# Co2Det.net
KiCad netlist of a schematic drawn in EAGLE
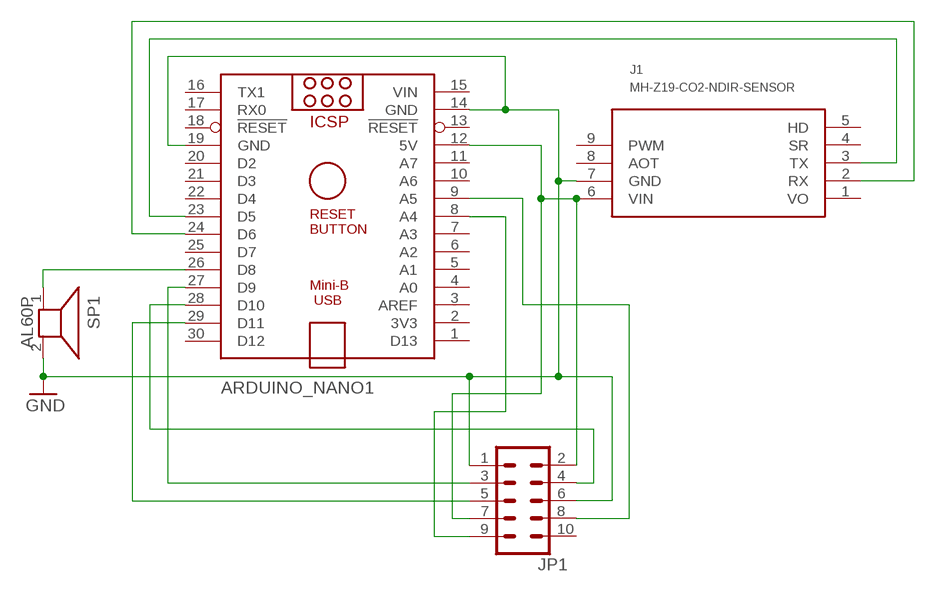
[diagram p0: schematic, sheet 1]

(export (version "E")
  (design (tool "Eeschema 10.0.6"))
  (components
    (comp (ref "ARDUINO_NANO1")
      (value "ARDUINO_NANO")
      (footprint "eagle-import:ARDUINO_NANO")
      (libsource (lib "eagle-import") (part "ARDUINO_NANO"))
    )
    (comp (ref "J1")
      (value "MH-Z19-CO2-NDIR-SENSOR")
      (footprint "eagle-import:MH-Z19")
      (libsource (lib "eagle-import") (part "MH-Z19-CO2-NDIR-SENSOR"))
    )
    (comp (ref "JP1")
      (value "ML10L")
      (footprint "eagle-import:ML10L")
      (libsource (lib "eagle-import") (part "ML10L"))
    )
    (comp (ref "SP1")
      (value "AL60P")
      (footprint "eagle-import:AL60P")
      (libsource (lib "eagle-import") (part "AL60P"))
    )
  )
  (nets
    (net (code "1") (name "/VIN") (class "Default")
      (node (ref "ARDUINO_NANO1") (pin "15") (pinfunction "VIN_15") (pintype "power_in"))
    )
    (net (code "2") (name "/VO") (class "Default")
      (node (ref "J1") (pin "1") (pinfunction "VO_1") (pintype "power_in"))
    )
    (net (code "3") (name "GND") (class "Default")
      (node (ref "ARDUINO_NANO1") (pin "14") (pinfunction "GND_14") (pintype "power_in"))
      (node (ref "ARDUINO_NANO1") (pin "19") (pinfunction "GND_19") (pintype "power_in"))
      (node (ref "J1") (pin "7") (pinfunction "GND_7") (pintype "power_in"))
      (node (ref "JP1") (pin "1") (pinfunction "1_1") (pintype "passive"))
      (node (ref "JP1") (pin "6") (pinfunction "6_6") (pintype "passive"))
      (node (ref "SP1") (pin "2") (pinfunction "2_2") (pintype "passive"))
    )
    (net (code "4") (name "Net-(ARDUINO_NANO1-5V)") (class "Default")
      (node (ref "ARDUINO_NANO1") (pin "12") (pinfunction "5V_12") (pintype "power_in"))
      (node (ref "J1") (pin "6") (pinfunction "VIN_6") (pintype "power_in"))
      (node (ref "JP1") (pin "2") (pinfunction "2_2") (pintype "passive"))
      (node (ref "JP1") (pin "7") (pinfunction "7_7") (pintype "passive"))
    )
    (net (code "5") (name "Net-(ARDUINO_NANO1-A4)") (class "Default")
      (node (ref "ARDUINO_NANO1") (pin "8") (pinfunction "A4_8") (pintype "bidirectional"))
      (node (ref "JP1") (pin "9") (pinfunction "9_9") (pintype "passive"))
    )
    (net (code "6") (name "Net-(ARDUINO_NANO1-A5)") (class "Default")
      (node (ref "ARDUINO_NANO1") (pin "9") (pinfunction "A5_9") (pintype "bidirectional"))
      (node (ref "JP1") (pin "8") (pinfunction "8_8") (pintype "passive"))
    )
    (net (code "7") (name "Net-(ARDUINO_NANO1-D5)") (class "Default")
      (node (ref "ARDUINO_NANO1") (pin "23") (pinfunction "D5_23") (pintype "bidirectional"))
      (node (ref "J1") (pin "3") (pinfunction "TX_3") (pintype "output"))
    )
    (net (code "8") (name "Net-(ARDUINO_NANO1-D6)") (class "Default")
      (node (ref "ARDUINO_NANO1") (pin "24") (pinfunction "D6_24") (pintype "bidirectional"))
      (node (ref "J1") (pin "2") (pinfunction "RX_2") (pintype "input"))
    )
    (net (code "9") (name "Net-(ARDUINO_NANO1-D8)") (class "Default")
      (node (ref "ARDUINO_NANO1") (pin "26") (pinfunction "D8_26") (pintype "bidirectional"))
      (node (ref "SP1") (pin "1") (pinfunction "1_1") (pintype "passive"))
    )
    (net (code "10") (name "Net-(ARDUINO_NANO1-D9)") (class "Default")
      (node (ref "ARDUINO_NANO1") (pin "27") (pinfunction "D9_27") (pintype "bidirectional"))
      (node (ref "JP1") (pin "3") (pinfunction "3_3") (pintype "passive"))
    )
    (net (code "11") (name "Net-(ARDUINO_NANO1-D10)") (class "Default")
      (node (ref "ARDUINO_NANO1") (pin "28") (pinfunction "D10_28") (pintype "bidirectional"))
      (node (ref "JP1") (pin "4") (pinfunction "4_4") (pintype "passive"))
    )
    (net (code "12") (name "Net-(ARDUINO_NANO1-D11)") (class "Default")
      (node (ref "ARDUINO_NANO1") (pin "29") (pinfunction "D11_29") (pintype "bidirectional"))
      (node (ref "JP1") (pin "5") (pinfunction "5_5") (pintype "passive"))
    )
    (net (code "13") (name "unconnected-(ARDUINO_NANO1-3V3-Pad2)") (class "Default")
      (node (ref "ARDUINO_NANO1") (pin "2") (pinfunction "3V3_2") (pintype "output"))
    )
    (net (code "14") (name "unconnected-(ARDUINO_NANO1-A0-Pad4)") (class "Default")
      (node (ref "ARDUINO_NANO1") (pin "4") (pinfunction "A0_4") (pintype "bidirectional"))
    )
    (net (code "15") (name "unconnected-(ARDUINO_NANO1-A1-Pad5)") (class "Default")
      (node (ref "ARDUINO_NANO1") (pin "5") (pinfunction "A1_5") (pintype "bidirectional"))
    )
    (net (code "16") (name "unconnected-(ARDUINO_NANO1-A2-Pad6)") (class "Default")
      (node (ref "ARDUINO_NANO1") (pin "6") (pinfunction "A2_6") (pintype "bidirectional"))
    )
    (net (code "17") (name "unconnected-(ARDUINO_NANO1-A3-Pad7)") (class "Default")
      (node (ref "ARDUINO_NANO1") (pin "7") (pinfunction "A3_7") (pintype "bidirectional"))
    )
    (net (code "18") (name "unconnected-(ARDUINO_NANO1-A6-Pad10)") (class "Default")
      (node (ref "ARDUINO_NANO1") (pin "10") (pinfunction "A6_10") (pintype "bidirectional"))
    )
    (net (code "19") (name "unconnected-(ARDUINO_NANO1-A7-Pad11)") (class "Default")
      (node (ref "ARDUINO_NANO1") (pin "11") (pinfunction "A7_11") (pintype "bidirectional"))
    )
    (net (code "20") (name "unconnected-(ARDUINO_NANO1-AREF-Pad3)") (class "Default")
      (node (ref "ARDUINO_NANO1") (pin "3") (pinfunction "AREF_3") (pintype "input"))
    )
    (net (code "21") (name "unconnected-(ARDUINO_NANO1-D2-Pad20)") (class "Default")
      (node (ref "ARDUINO_NANO1") (pin "20") (pinfunction "D2_20") (pintype "bidirectional"))
    )
    (net (code "22") (name "unconnected-(ARDUINO_NANO1-D3-Pad21)") (class "Default")
      (node (ref "ARDUINO_NANO1") (pin "21") (pinfunction "D3_21") (pintype "bidirectional"))
    )
    (net (code "23") (name "unconnected-(ARDUINO_NANO1-D4-Pad22)") (class "Default")
      (node (ref "ARDUINO_NANO1") (pin "22") (pinfunction "D4_22") (pintype "bidirectional"))
    )
    (net (code "24") (name "unconnected-(ARDUINO_NANO1-D7-Pad25)") (class "Default")
      (node (ref "ARDUINO_NANO1") (pin "25") (pinfunction "D7_25") (pintype "bidirectional"))
    )
    (net (code "25") (name "unconnected-(ARDUINO_NANO1-D12-Pad30)") (class "Default")
      (node (ref "ARDUINO_NANO1") (pin "30") (pinfunction "D12_30") (pintype "bidirectional"))
    )
    (net (code "26") (name "unconnected-(ARDUINO_NANO1-D13-Pad1)") (class "Default")
      (node (ref "ARDUINO_NANO1") (pin "1") (pinfunction "D13_1") (pintype "bidirectional"))
    )
    (net (code "27") (name "unconnected-(ARDUINO_NANO1-RX0-Pad17)") (class "Default")
      (node (ref "ARDUINO_NANO1") (pin "17") (pinfunction "RX0_17") (pintype "bidirectional"))
    )
    (net (code "28") (name "unconnected-(ARDUINO_NANO1-TX1-Pad16)") (class "Default")
      (node (ref "ARDUINO_NANO1") (pin "16") (pinfunction "TX1_16") (pintype "bidirectional"))
    )
    (net (code "29") (name "unconnected-(ARDUINO_NANO1-~{RESET}-Pad13)") (class "Default")
      (node (ref "ARDUINO_NANO1") (pin "13") (pinfunction "~{RESET}_13") (pintype "input"))
    )
    (net (code "30") (name "unconnected-(ARDUINO_NANO1-~{RESET}-Pad18)") (class "Default")
      (node (ref "ARDUINO_NANO1") (pin "18") (pinfunction "~{RESET}_18") (pintype "input"))
    )
    (net (code "31") (name "unconnected-(J1-AOT-Pad8)") (class "Default")
      (node (ref "J1") (pin "8") (pinfunction "AOT_8") (pintype "no_connect"))
    )
    (net (code "32") (name "unconnected-(J1-HD-Pad5)") (class "Default")
      (node (ref "J1") (pin "5") (pinfunction "HD_5") (pintype "input"))
    )
    (net (code "33") (name "unconnected-(J1-PWM-Pad9)") (class "Default")
      (node (ref "J1") (pin "9") (pinfunction "PWM_9") (pintype "output"))
    )
    (net (code "34") (name "unconnected-(J1-SR-Pad4)") (class "Default")
      (node (ref "J1") (pin "4") (pinfunction "SR_4") (pintype "no_connect"))
    )
    (net (code "35") (name "unconnected-(JP1-Pad10)") (class "Default")
      (node (ref "JP1") (pin "10") (pinfunction "10_10") (pintype "passive"))
    )
  )
)
